# PL_Conenctor.net
KiCad netlist of a schematic drawn in Altium Designer
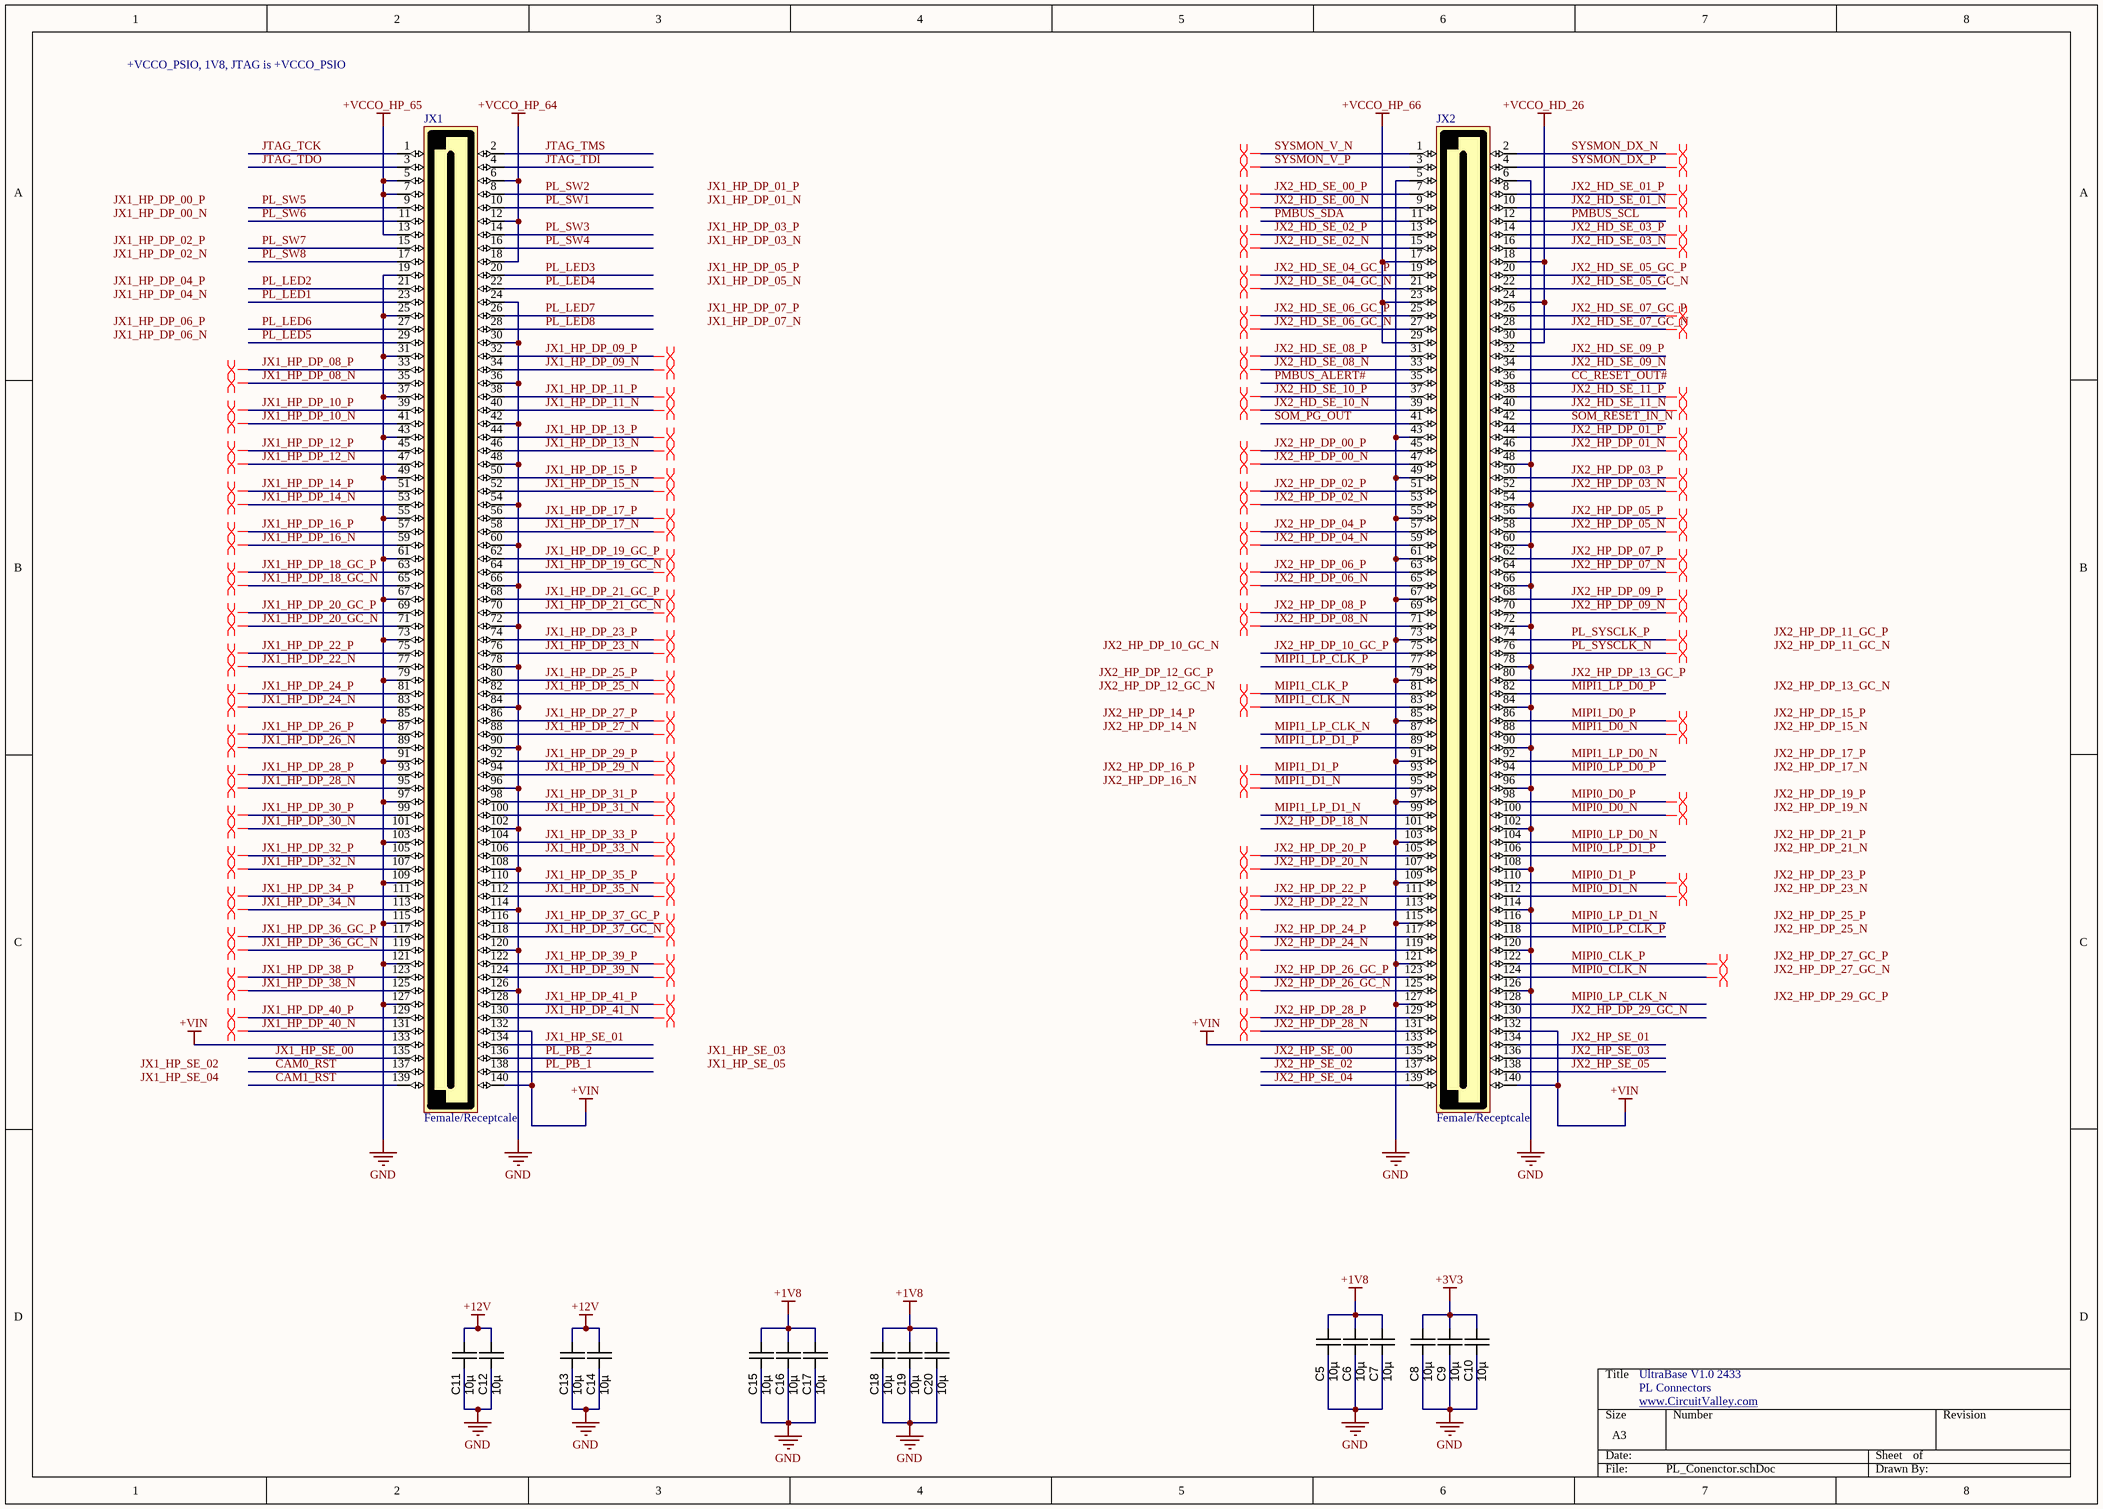
[diagram p0: PL_Conenctor.schDoc]

(export (version "E")
  (design (tool "Eeschema 10.0.6"))
  (components
    (comp (ref "C5")
      (value "10µ")
      (footprint "CAPC3225N")
      (description "Capacitor SMD Cer 10uF 20% 16V X5R 1210")
      (fields (field (name "TOLERANCE") "±20%"))
      (libsource (lib "PBL - Capacitors") (part "CAPC_10u_1210_50V"))
    )
    (comp (ref "C6")
      (value "10µ")
      (footprint "CAPC3225N")
      (description "Capacitor SMD Cer 10uF 20% 16V X5R 1210")
      (fields (field (name "TOLERANCE") "±20%"))
      (libsource (lib "PBL - Capacitors") (part "CAPC_10u_1210_50V"))
    )
    (comp (ref "C7")
      (value "10µ")
      (footprint "CAPC3225N")
      (description "Capacitor SMD Cer 10uF 20% 16V X5R 1210")
      (fields (field (name "TOLERANCE") "±20%"))
      (libsource (lib "PBL - Capacitors") (part "CAPC_10u_1210_50V"))
    )
    (comp (ref "C8")
      (value "10µ")
      (footprint "CAPC3225N")
      (description "Capacitor SMD Cer 10uF 20% 16V X5R 1210")
      (fields (field (name "TOLERANCE") "±20%"))
      (libsource (lib "PBL - Capacitors") (part "CAPC_10u_1210_50V"))
    )
    (comp (ref "C9")
      (value "10µ")
      (footprint "CAPC3225N")
      (description "Capacitor SMD Cer 10uF 20% 16V X5R 1210")
      (fields (field (name "TOLERANCE") "±20%"))
      (libsource (lib "PBL - Capacitors") (part "CAPC_10u_1210_50V"))
    )
    (comp (ref "C10")
      (value "10µ")
      (footprint "CAPC3225N")
      (description "Capacitor SMD Cer 10uF 20% 16V X5R 1210")
      (fields (field (name "TOLERANCE") "±20%"))
      (libsource (lib "PBL - Capacitors") (part "CAPC_10u_1210_50V"))
    )
    (comp (ref "C11")
      (value "10µ")
      (footprint "CAPC3225N")
      (description "Capacitor SMD Cer 10uF 20% 16V X5R 1210")
      (fields (field (name "TOLERANCE") "±20%"))
      (libsource (lib "PBL - Capacitors") (part "CAPC_10u_1210_50V"))
    )
    (comp (ref "C12")
      (value "10µ")
      (footprint "CAPC3225N")
      (description "Capacitor SMD Cer 10uF 20% 16V X5R 1210")
      (fields (field (name "TOLERANCE") "±20%"))
      (libsource (lib "PBL - Capacitors") (part "CAPC_10u_1210_50V"))
    )
    (comp (ref "C13")
      (value "10µ")
      (footprint "CAPC3225N")
      (description "Capacitor SMD Cer 10uF 20% 16V X5R 1210")
      (fields (field (name "TOLERANCE") "±20%"))
      (libsource (lib "PBL - Capacitors") (part "CAPC_10u_1210_50V"))
    )
    (comp (ref "C14")
      (value "10µ")
      (footprint "CAPC3225N")
      (description "Capacitor SMD Cer 10uF 20% 16V X5R 1210")
      (fields (field (name "TOLERANCE") "±20%"))
      (libsource (lib "PBL - Capacitors") (part "CAPC_10u_1210_50V"))
    )
    (comp (ref "C15")
      (value "10µ")
      (footprint "CAPC3225N")
      (description "Capacitor SMD Cer 10uF 20% 16V X5R 1210")
      (fields (field (name "TOLERANCE") "±20%"))
      (libsource (lib "PBL - Capacitors") (part "CAPC_10u_1210_50V"))
    )
    (comp (ref "C16")
      (value "10µ")
      (footprint "CAPC3225N")
      (description "Capacitor SMD Cer 10uF 20% 16V X5R 1210")
      (fields (field (name "TOLERANCE") "±20%"))
      (libsource (lib "PBL - Capacitors") (part "CAPC_10u_1210_50V"))
    )
    (comp (ref "C17")
      (value "10µ")
      (footprint "CAPC3225N")
      (description "Capacitor SMD Cer 10uF 20% 16V X5R 1210")
      (fields (field (name "TOLERANCE") "±20%"))
      (libsource (lib "PBL - Capacitors") (part "CAPC_10u_1210_50V"))
    )
    (comp (ref "C18")
      (value "10µ")
      (footprint "CAPC3225N")
      (description "Capacitor SMD Cer 10uF 20% 16V X5R 1210")
      (fields (field (name "TOLERANCE") "±20%"))
      (libsource (lib "PBL - Capacitors") (part "CAPC_10u_1210_50V"))
    )
    (comp (ref "C19")
      (value "10µ")
      (footprint "CAPC3225N")
      (description "Capacitor SMD Cer 10uF 20% 16V X5R 1210")
      (fields (field (name "TOLERANCE") "±20%"))
      (libsource (lib "PBL - Capacitors") (part "CAPC_10u_1210_50V"))
    )
    (comp (ref "C20")
      (value "10µ")
      (footprint "CAPC3225N")
      (description "Capacitor SMD Cer 10uF 20% 16V X5R 1210")
      (fields (field (name "TOLERANCE") "±20%"))
      (libsource (lib "PBL - Capacitors") (part "CAPC_10u_1210_50V"))
    )
    (comp (ref "JX1")
      (value "Female/Receptcale")
      (footprint "5177985-6")
      (description "140 Pin Ultrascale  SOM Connector with ultrazed specific SOM net delay")
      (libsource (lib "cvlib") (part "5177985-6_Ultrazed_JX1"))
    )
    (comp (ref "JX2")
      (value "Female/Receptcale")
      (footprint "5177985-6")
      (description "140 Pin Ultrascale  SOM Connector with ultrazed specific SOM net delay")
      (libsource (lib "cvlib") (part "5177985-6_Ultrazed_JX2"))
    )
  )
  (nets
    (net (code "1") (name "+1V8") (class "Default")
      (node (ref "C15") (pin "1") (pintype "passive"))
      (node (ref "C16") (pin "1") (pintype "passive"))
      (node (ref "C17") (pin "1") (pintype "passive"))
      (node (ref "C18") (pin "1") (pintype "passive"))
      (node (ref "C19") (pin "1") (pintype "passive"))
      (node (ref "C20") (pin "1") (pintype "passive"))
      (node (ref "C5") (pin "1") (pintype "passive"))
      (node (ref "C6") (pin "1") (pintype "passive"))
      (node (ref "C7") (pin "1") (pintype "passive"))
    )
    (net (code "2") (name "+3V3") (class "Default")
      (node (ref "C10") (pin "1") (pintype "passive"))
      (node (ref "C8") (pin "1") (pintype "passive"))
      (node (ref "C9") (pin "1") (pintype "passive"))
    )
    (net (code "3") (name "+12V") (class "Default")
      (node (ref "C11") (pin "1") (pintype "passive"))
      (node (ref "C12") (pin "1") (pintype "passive"))
      (node (ref "C13") (pin "1") (pintype "passive"))
      (node (ref "C14") (pin "1") (pintype "passive"))
    )
    (net (code "4") (name "+VCCO_HD_26") (class "Default")
      (node (ref "JX2") (pin "18") (pintype "bidirectional"))
      (node (ref "JX2") (pin "24") (pintype "bidirectional"))
      (node (ref "JX2") (pin "30") (pintype "bidirectional"))
    )
    (net (code "5") (name "+VCCO_HP_64") (class "Default")
      (node (ref "JX1") (pin "12") (pintype "bidirectional"))
      (node (ref "JX1") (pin "18") (pintype "bidirectional"))
      (node (ref "JX1") (pin "6") (pintype "bidirectional"))
    )
    (net (code "6") (name "+VCCO_HP_65") (class "Default")
      (node (ref "JX1") (pin "13") (pintype "bidirectional"))
      (node (ref "JX1") (pin "5") (pintype "bidirectional"))
      (node (ref "JX1") (pin "7") (pintype "bidirectional"))
    )
    (net (code "7") (name "+VCCO_HP_66") (class "Default")
      (node (ref "JX2") (pin "17") (pintype "bidirectional"))
      (node (ref "JX2") (pin "23") (pintype "bidirectional"))
      (node (ref "JX2") (pin "29") (pintype "bidirectional"))
    )
    (net (code "8") (name "+VIN") (class "Default")
      (node (ref "JX1") (pin "132") (pintype "bidirectional"))
      (node (ref "JX1") (pin "133") (pintype "bidirectional"))
      (node (ref "JX1") (pin "140") (pintype "bidirectional"))
      (node (ref "JX2") (pin "132") (pintype "bidirectional"))
      (node (ref "JX2") (pin "133") (pintype "bidirectional"))
      (node (ref "JX2") (pin "140") (pintype "bidirectional"))
    )
    (net (code "9") (name "/CAM0_RST") (class "Default")
      (node (ref "JX1") (pin "137") (pintype "bidirectional"))
    )
    (net (code "10") (name "/CAM1_RST") (class "Default")
      (node (ref "JX1") (pin "139") (pintype "bidirectional"))
    )
    (net (code "11") (name "/CC_RESET_OUT#") (class "Default")
      (node (ref "JX2") (pin "36") (pintype "bidirectional"))
    )
    (net (code "12") (name "/JTAG_TCK") (class "Default")
      (node (ref "JX1") (pin "1") (pintype "bidirectional"))
    )
    (net (code "13") (name "/JTAG_TDI") (class "Default")
      (node (ref "JX1") (pin "4") (pintype "bidirectional"))
    )
    (net (code "14") (name "/JTAG_TDO") (class "Default")
      (node (ref "JX1") (pin "3") (pintype "bidirectional"))
    )
    (net (code "15") (name "/JTAG_TMS") (class "Default")
      (node (ref "JX1") (pin "2") (pintype "bidirectional"))
    )
    (net (code "32") (name "/JX1_HP_DP_08_N") (class "Default")
      (node (ref "JX1") (pin "35") (pintype "bidirectional"))
    )
    (net (code "33") (name "/JX1_HP_DP_08_P") (class "Default")
      (node (ref "JX1") (pin "33") (pintype "bidirectional"))
    )
    (net (code "34") (name "/JX1_HP_DP_09_N") (class "Default")
      (node (ref "JX1") (pin "34") (pintype "bidirectional"))
    )
    (net (code "35") (name "/JX1_HP_DP_09_P") (class "Default")
      (node (ref "JX1") (pin "32") (pintype "bidirectional"))
    )
    (net (code "36") (name "/JX1_HP_DP_10_N") (class "Default")
      (node (ref "JX1") (pin "41") (pintype "bidirectional"))
    )
    (net (code "37") (name "/JX1_HP_DP_10_P") (class "Default")
      (node (ref "JX1") (pin "39") (pintype "bidirectional"))
    )
    (net (code "38") (name "/JX1_HP_DP_11_N") (class "Default")
      (node (ref "JX1") (pin "40") (pintype "bidirectional"))
    )
    (net (code "39") (name "/JX1_HP_DP_11_P") (class "Default")
      (node (ref "JX1") (pin "38") (pintype "bidirectional"))
    )
    (net (code "40") (name "/JX1_HP_DP_12_N") (class "Default")
      (node (ref "JX1") (pin "47") (pintype "bidirectional"))
    )
    (net (code "41") (name "/JX1_HP_DP_12_P") (class "Default")
      (node (ref "JX1") (pin "45") (pintype "bidirectional"))
    )
    (net (code "42") (name "/JX1_HP_DP_13_N") (class "Default")
      (node (ref "JX1") (pin "46") (pintype "bidirectional"))
    )
    (net (code "43") (name "/JX1_HP_DP_13_P") (class "Default")
      (node (ref "JX1") (pin "44") (pintype "bidirectional"))
    )
    (net (code "44") (name "/JX1_HP_DP_14_N") (class "Default")
      (node (ref "JX1") (pin "53") (pintype "bidirectional"))
    )
    (net (code "45") (name "/JX1_HP_DP_14_P") (class "Default")
      (node (ref "JX1") (pin "51") (pintype "bidirectional"))
    )
    (net (code "46") (name "/JX1_HP_DP_15_N") (class "Default")
      (node (ref "JX1") (pin "52") (pintype "bidirectional"))
    )
    (net (code "47") (name "/JX1_HP_DP_15_P") (class "Default")
      (node (ref "JX1") (pin "50") (pintype "bidirectional"))
    )
    (net (code "48") (name "/JX1_HP_DP_16_N") (class "Default")
      (node (ref "JX1") (pin "59") (pintype "bidirectional"))
    )
    (net (code "49") (name "/JX1_HP_DP_16_P") (class "Default")
      (node (ref "JX1") (pin "57") (pintype "bidirectional"))
    )
    (net (code "50") (name "/JX1_HP_DP_17_N") (class "Default")
      (node (ref "JX1") (pin "58") (pintype "bidirectional"))
    )
    (net (code "51") (name "/JX1_HP_DP_17_P") (class "Default")
      (node (ref "JX1") (pin "56") (pintype "bidirectional"))
    )
    (net (code "52") (name "/JX1_HP_DP_18_GC_N") (class "Default")
      (node (ref "JX1") (pin "65") (pintype "bidirectional"))
    )
    (net (code "53") (name "/JX1_HP_DP_18_GC_P") (class "Default")
      (node (ref "JX1") (pin "63") (pintype "bidirectional"))
    )
    (net (code "54") (name "/JX1_HP_DP_19_GC_N") (class "Default")
      (node (ref "JX1") (pin "64") (pintype "bidirectional"))
    )
    (net (code "55") (name "/JX1_HP_DP_19_GC_P") (class "Default")
      (node (ref "JX1") (pin "62") (pintype "bidirectional"))
    )
    (net (code "56") (name "/JX1_HP_DP_20_GC_N") (class "Default")
      (node (ref "JX1") (pin "71") (pintype "bidirectional"))
    )
    (net (code "57") (name "/JX1_HP_DP_20_GC_P") (class "Default")
      (node (ref "JX1") (pin "69") (pintype "bidirectional"))
    )
    (net (code "58") (name "/JX1_HP_DP_21_GC_N") (class "Default")
      (node (ref "JX1") (pin "70") (pintype "bidirectional"))
    )
    (net (code "59") (name "/JX1_HP_DP_21_GC_P") (class "Default")
      (node (ref "JX1") (pin "68") (pintype "bidirectional"))
    )
    (net (code "60") (name "/JX1_HP_DP_22_N") (class "Default")
      (node (ref "JX1") (pin "77") (pintype "bidirectional"))
    )
    (net (code "61") (name "/JX1_HP_DP_22_P") (class "Default")
      (node (ref "JX1") (pin "75") (pintype "bidirectional"))
    )
    (net (code "62") (name "/JX1_HP_DP_23_N") (class "Default")
      (node (ref "JX1") (pin "76") (pintype "bidirectional"))
    )
    (net (code "63") (name "/JX1_HP_DP_23_P") (class "Default")
      (node (ref "JX1") (pin "74") (pintype "bidirectional"))
    )
    (net (code "64") (name "/JX1_HP_DP_24_N") (class "Default")
      (node (ref "JX1") (pin "83") (pintype "bidirectional"))
    )
    (net (code "65") (name "/JX1_HP_DP_24_P") (class "Default")
      (node (ref "JX1") (pin "81") (pintype "bidirectional"))
    )
    (net (code "66") (name "/JX1_HP_DP_25_N") (class "Default")
      (node (ref "JX1") (pin "82") (pintype "bidirectional"))
    )
    (net (code "67") (name "/JX1_HP_DP_25_P") (class "Default")
      (node (ref "JX1") (pin "80") (pintype "bidirectional"))
    )
    (net (code "68") (name "/JX1_HP_DP_26_N") (class "Default")
      (node (ref "JX1") (pin "89") (pintype "bidirectional"))
    )
    (net (code "69") (name "/JX1_HP_DP_26_P") (class "Default")
      (node (ref "JX1") (pin "87") (pintype "bidirectional"))
    )
    (net (code "70") (name "/JX1_HP_DP_27_N") (class "Default")
      (node (ref "JX1") (pin "88") (pintype "bidirectional"))
    )
    (net (code "71") (name "/JX1_HP_DP_27_P") (class "Default")
      (node (ref "JX1") (pin "86") (pintype "bidirectional"))
    )
    (net (code "72") (name "/JX1_HP_DP_28_N") (class "Default")
      (node (ref "JX1") (pin "95") (pintype "bidirectional"))
    )
    (net (code "73") (name "/JX1_HP_DP_28_P") (class "Default")
      (node (ref "JX1") (pin "93") (pintype "bidirectional"))
    )
    (net (code "74") (name "/JX1_HP_DP_29_N") (class "Default")
      (node (ref "JX1") (pin "94") (pintype "bidirectional"))
    )
    (net (code "75") (name "/JX1_HP_DP_29_P") (class "Default")
      (node (ref "JX1") (pin "92") (pintype "bidirectional"))
    )
    (net (code "76") (name "/JX1_HP_DP_30_N") (class "Default")
      (node (ref "JX1") (pin "101") (pintype "bidirectional"))
    )
    (net (code "77") (name "/JX1_HP_DP_30_P") (class "Default")
      (node (ref "JX1") (pin "99") (pintype "bidirectional"))
    )
    (net (code "78") (name "/JX1_HP_DP_31_N") (class "Default")
      (node (ref "JX1") (pin "100") (pintype "bidirectional"))
    )
    (net (code "79") (name "/JX1_HP_DP_31_P") (class "Default")
      (node (ref "JX1") (pin "98") (pintype "bidirectional"))
    )
    (net (code "80") (name "/JX1_HP_DP_32_N") (class "Default")
      (node (ref "JX1") (pin "107") (pintype "bidirectional"))
    )
    (net (code "81") (name "/JX1_HP_DP_32_P") (class "Default")
      (node (ref "JX1") (pin "105") (pintype "bidirectional"))
    )
    (net (code "82") (name "/JX1_HP_DP_33_N") (class "Default")
      (node (ref "JX1") (pin "106") (pintype "bidirectional"))
    )
    (net (code "83") (name "/JX1_HP_DP_33_P") (class "Default")
      (node (ref "JX1") (pin "104") (pintype "bidirectional"))
    )
    (net (code "84") (name "/JX1_HP_DP_34_N") (class "Default")
      (node (ref "JX1") (pin "113") (pintype "bidirectional"))
    )
    (net (code "85") (name "/JX1_HP_DP_34_P") (class "Default")
      (node (ref "JX1") (pin "111") (pintype "bidirectional"))
    )
    (net (code "86") (name "/JX1_HP_DP_35_N") (class "Default")
      (node (ref "JX1") (pin "112") (pintype "bidirectional"))
    )
    (net (code "87") (name "/JX1_HP_DP_35_P") (class "Default")
      (node (ref "JX1") (pin "110") (pintype "bidirectional"))
    )
    (net (code "88") (name "/JX1_HP_DP_36_GC_N") (class "Default")
      (node (ref "JX1") (pin "119") (pintype "bidirectional"))
    )
    (net (code "89") (name "/JX1_HP_DP_36_GC_P") (class "Default")
      (node (ref "JX1") (pin "117") (pintype "bidirectional"))
    )
    (net (code "90") (name "/JX1_HP_DP_37_GC_N") (class "Default")
      (node (ref "JX1") (pin "118") (pintype "bidirectional"))
    )
    (net (code "91") (name "/JX1_HP_DP_37_GC_P") (class "Default")
      (node (ref "JX1") (pin "116") (pintype "bidirectional"))
    )
    (net (code "92") (name "/JX1_HP_DP_38_N") (class "Default")
      (node (ref "JX1") (pin "125") (pintype "bidirectional"))
    )
    (net (code "93") (name "/JX1_HP_DP_38_P") (class "Default")
      (node (ref "JX1") (pin "123") (pintype "bidirectional"))
    )
    (net (code "94") (name "/JX1_HP_DP_39_N") (class "Default")
      (node (ref "JX1") (pin "124") (pintype "bidirectional"))
    )
    (net (code "95") (name "/JX1_HP_DP_39_P") (class "Default")
      (node (ref "JX1") (pin "122") (pintype "bidirectional"))
    )
    (net (code "96") (name "/JX1_HP_DP_40_N") (class "Default")
      (node (ref "JX1") (pin "131") (pintype "bidirectional"))
    )
    (net (code "97") (name "/JX1_HP_DP_40_P") (class "Default")
      (node (ref "JX1") (pin "129") (pintype "bidirectional"))
    )
    (net (code "98") (name "/JX1_HP_DP_41_N") (class "Default")
      (node (ref "JX1") (pin "130") (pintype "bidirectional"))
    )
    (net (code "99") (name "/JX1_HP_DP_41_P") (class "Default")
      (node (ref "JX1") (pin "128") (pintype "bidirectional"))
    )
    (net (code "100") (name "/JX1_HP_SE_00") (class "Default")
      (node (ref "JX1") (pin "135") (pintype "bidirectional"))
    )
    (net (code "101") (name "/JX1_HP_SE_01") (class "Default")
      (node (ref "JX1") (pin "134") (pintype "bidirectional"))
    )
    (net (code "106") (name "/JX2_HD_SE_00_N") (class "Default")
      (node (ref "JX2") (pin "9") (pintype "bidirectional"))
    )
    (net (code "107") (name "/JX2_HD_SE_00_P") (class "Default")
      (node (ref "JX2") (pin "7") (pintype "bidirectional"))
    )
    (net (code "108") (name "/JX2_HD_SE_01_N") (class "Default")
      (node (ref "JX2") (pin "10") (pintype "bidirectional"))
    )
    (net (code "109") (name "/JX2_HD_SE_01_P") (class "Default")
      (node (ref "JX2") (pin "8") (pintype "bidirectional"))
    )
    (net (code "110") (name "/JX2_HD_SE_02_N") (class "Default")
      (node (ref "JX2") (pin "15") (pintype "bidirectional"))
    )
    (net (code "111") (name "/JX2_HD_SE_02_P") (class "Default")
      (node (ref "JX2") (pin "13") (pintype "bidirectional"))
    )
    (net (code "112") (name "/JX2_HD_SE_03_N") (class "Default")
      (node (ref "JX2") (pin "16") (pintype "bidirectional"))
    )
    (net (code "113") (name "/JX2_HD_SE_03_P") (class "Default")
      (node (ref "JX2") (pin "14") (pintype "bidirectional"))
    )
    (net (code "114") (name "/JX2_HD_SE_04_GC_N") (class "Default")
      (node (ref "JX2") (pin "21") (pintype "bidirectional"))
    )
    (net (code "115") (name "/JX2_HD_SE_04_GC_P") (class "Default")
      (node (ref "JX2") (pin "19") (pintype "bidirectional"))
    )
    (net (code "116") (name "/JX2_HD_SE_05_GC_N") (class "Default")
      (node (ref "JX2") (pin "22") (pintype "bidirectional"))
    )
    (net (code "117") (name "/JX2_HD_SE_05_GC_P") (class "Default")
      (node (ref "JX2") (pin "20") (pintype "bidirectional"))
    )
    (net (code "118") (name "/JX2_HD_SE_06_GC_N") (class "Default")
      (node (ref "JX2") (pin "27") (pintype "bidirectional"))
    )
    (net (code "119") (name "/JX2_HD_SE_06_GC_P") (class "Default")
      (node (ref "JX2") (pin "25") (pintype "bidirectional"))
    )
    (net (code "120") (name "/JX2_HD_SE_07_GC_N") (class "Default")
      (node (ref "JX2") (pin "28") (pintype "bidirectional"))
    )
    (net (code "121") (name "/JX2_HD_SE_07_GC_P") (class "Default")
      (node (ref "JX2") (pin "26") (pintype "bidirectional"))
    )
    (net (code "122") (name "/JX2_HD_SE_08_N") (class "Default")
      (node (ref "JX2") (pin "33") (pintype "bidirectional"))
    )
    (net (code "123") (name "/JX2_HD_SE_08_P") (class "Default")
      (node (ref "JX2") (pin "31") (pintype "bidirectional"))
    )
    (net (code "124") (name "/JX2_HD_SE_09_N") (class "Default")
      (node (ref "JX2") (pin "34") (pintype "bidirectional"))
    )
    (net (code "125") (name "/JX2_HD_SE_09_P") (class "Default")
      (node (ref "JX2") (pin "32") (pintype "bidirectional"))
    )
    (net (code "126") (name "/JX2_HD_SE_10_N") (class "Default")
      (node (ref "JX2") (pin "39") (pintype "bidirectional"))
    )
    (net (code "127") (name "/JX2_HD_SE_10_P") (class "Default")
      (node (ref "JX2") (pin "37") (pintype "bidirectional"))
    )
    (net (code "128") (name "/JX2_HD_SE_11_N") (class "Default")
      (node (ref "JX2") (pin "40") (pintype "bidirectional"))
    )
    (net (code "129") (name "/JX2_HD_SE_11_P") (class "Default")
      (node (ref "JX2") (pin "38") (pintype "bidirectional"))
    )
    (net (code "130") (name "/JX2_HP_DP_00_N") (class "Default")
      (node (ref "JX2") (pin "47") (pintype "bidirectional"))
    )
    (net (code "131") (name "/JX2_HP_DP_00_P") (class "Default")
      (node (ref "JX2") (pin "45") (pintype "bidirectional"))
    )
    (net (code "132") (name "/JX2_HP_DP_01_N") (class "Default")
      (node (ref "JX2") (pin "46") (pintype "bidirectional"))
    )
    (net (code "133") (name "/JX2_HP_DP_01_P") (class "Default")
      (node (ref "JX2") (pin "44") (pintype "bidirectional"))
    )
    (net (code "134") (name "/JX2_HP_DP_02_N") (class "Default")
      (node (ref "JX2") (pin "53") (pintype "bidirectional"))
    )
    (net (code "135") (name "/JX2_HP_DP_02_P") (class "Default")
      (node (ref "JX2") (pin "51") (pintype "bidirectional"))
    )
    (net (code "136") (name "/JX2_HP_DP_03_N") (class "Default")
      (node (ref "JX2") (pin "52") (pintype "bidirectional"))
    )
    (net (code "137") (name "/JX2_HP_DP_03_P") (class "Default")
      (node (ref "JX2") (pin "50") (pintype "bidirectional"))
    )
    (net (code "138") (name "/JX2_HP_DP_04_N") (class "Default")
      (node (ref "JX2") (pin "59") (pintype "bidirectional"))
    )
    (net (code "139") (name "/JX2_HP_DP_04_P") (class "Default")
      (node (ref "JX2") (pin "57") (pintype "bidirectional"))
    )
    (net (code "140") (name "/JX2_HP_DP_05_N") (class "Default")
      (node (ref "JX2") (pin "58") (pintype "bidirectional"))
    )
    (net (code "141") (name "/JX2_HP_DP_05_P") (class "Default")
      (node (ref "JX2") (pin "56") (pintype "bidirectional"))
    )
    (net (code "142") (name "/JX2_HP_DP_06_N") (class "Default")
      (node (ref "JX2") (pin "65") (pintype "bidirectional"))
    )
    (net (code "143") (name "/JX2_HP_DP_06_P") (class "Default")
      (node (ref "JX2") (pin "63") (pintype "bidirectional"))
    )
    (net (code "144") (name "/JX2_HP_DP_07_N") (class "Default")
      (node (ref "JX2") (pin "64") (pintype "bidirectional"))
    )
    (net (code "145") (name "/JX2_HP_DP_07_P") (class "Default")
      (node (ref "JX2") (pin "62") (pintype "bidirectional"))
    )
    (net (code "146") (name "/JX2_HP_DP_08_N") (class "Default")
      (node (ref "JX2") (pin "71") (pintype "bidirectional"))
    )
    (net (code "147") (name "/JX2_HP_DP_08_P") (class "Default")
      (node (ref "JX2") (pin "69") (pintype "bidirectional"))
    )
    (net (code "148") (name "/JX2_HP_DP_09_N") (class "Default")
      (node (ref "JX2") (pin "70") (pintype "bidirectional"))
    )
    (net (code "149") (name "/JX2_HP_DP_09_P") (class "Default")
      (node (ref "JX2") (pin "68") (pintype "bidirectional"))
    )
    (net (code "151") (name "/JX2_HP_DP_10_GC_P") (class "Default")
      (node (ref "JX2") (pin "75") (pintype "bidirectional"))
    )
    (net (code "157") (name "/JX2_HP_DP_13_GC_P") (class "Default")
      (node (ref "JX2") (pin "80") (pintype "bidirectional"))
    )
    (net (code "166") (name "/JX2_HP_DP_18_N") (class "Default")
      (node (ref "JX2") (pin "101") (pintype "bidirectional"))
    )
    (net (code "169") (name "/JX2_HP_DP_20_N") (class "Default")
      (node (ref "JX2") (pin "107") (pintype "bidirectional"))
    )
    (net (code "170") (name "/JX2_HP_DP_20_P") (class "Default")
      (node (ref "JX2") (pin "105") (pintype "bidirectional"))
    )
    (net (code "173") (name "/JX2_HP_DP_22_N") (class "Default")
      (node (ref "JX2") (pin "113") (pintype "bidirectional"))
    )
    (net (code "174") (name "/JX2_HP_DP_22_P") (class "Default")
      (node (ref "JX2") (pin "111") (pintype "bidirectional"))
    )
    (net (code "177") (name "/JX2_HP_DP_24_N") (class "Default")
      (node (ref "JX2") (pin "119") (pintype "bidirectional"))
    )
    (net (code "178") (name "/JX2_HP_DP_24_P") (class "Default")
      (node (ref "JX2") (pin "117") (pintype "bidirectional"))
    )
    (net (code "181") (name "/JX2_HP_DP_26_GC_N") (class "Default")
      (node (ref "JX2") (pin "125") (pintype "bidirectional"))
    )
    (net (code "182") (name "/JX2_HP_DP_26_GC_P") (class "Default")
      (node (ref "JX2") (pin "123") (pintype "bidirectional"))
    )
    (net (code "185") (name "/JX2_HP_DP_28_N") (class "Default")
      (node (ref "JX2") (pin "131") (pintype "bidirectional"))
    )
    (net (code "186") (name "/JX2_HP_DP_28_P") (class "Default")
      (node (ref "JX2") (pin "129") (pintype "bidirectional"))
    )
    (net (code "187") (name "/JX2_HP_DP_29_GC_N") (class "Default")
      (node (ref "JX2") (pin "130") (pintype "bidirectional"))
    )
    (net (code "189") (name "/JX2_HP_SE_00") (class "Default")
      (node (ref "JX2") (pin "135") (pintype "bidirectional"))
    )
    (net (code "190") (name "/JX2_HP_SE_01") (class "Default")
      (node (ref "JX2") (pin "134") (pintype "bidirectional"))
    )
    (net (code "191") (name "/JX2_HP_SE_02") (class "Default")
      (node (ref "JX2") (pin "137") (pintype "bidirectional"))
    )
    (net (code "192") (name "/JX2_HP_SE_03") (class "Default")
      (node (ref "JX2") (pin "136") (pintype "bidirectional"))
    )
    (net (code "193") (name "/JX2_HP_SE_04") (class "Default")
      (node (ref "JX2") (pin "139") (pintype "bidirectional"))
    )
    (net (code "194") (name "/JX2_HP_SE_05") (class "Default")
      (node (ref "JX2") (pin "138") (pintype "bidirectional"))
    )
    (net (code "195") (name "/MIPI0_CLK_N") (class "Default")
      (node (ref "JX2") (pin "124") (pintype "bidirectional"))
    )
    (net (code "196") (name "/MIPI0_CLK_P") (class "Default")
      (node (ref "JX2") (pin "122") (pintype "bidirectional"))
    )
    (net (code "197") (name "/MIPI0_D0_N") (class "Default")
      (node (ref "JX2") (pin "100") (pintype "bidirectional"))
    )
    (net (code "198") (name "/MIPI0_D0_P") (class "Default")
      (node (ref "JX2") (pin "98") (pintype "bidirectional"))
    )
    (net (code "199") (name "/MIPI0_D1_N") (class "Default")
      (node (ref "JX2") (pin "112") (pintype "bidirectional"))
    )
    (net (code "200") (name "/MIPI0_D1_P") (class "Default")
      (node (ref "JX2") (pin "110") (pintype "bidirectional"))
    )
    (net (code "201") (name "/MIPI0_LP_CLK_N") (class "Default")
      (node (ref "JX2") (pin "128") (pintype "bidirectional"))
    )
    (net (code "202") (name "/MIPI0_LP_CLK_P") (class "Default")
      (node (ref "JX2") (pin "118") (pintype "bidirectional"))
    )
    (net (code "203") (name "/MIPI0_LP_D0_N") (class "Default")
      (node (ref "JX2") (pin "104") (pintype "bidirectional"))
    )
    (net (code "204") (name "/MIPI0_LP_D0_P") (class "Default")
      (node (ref "JX2") (pin "94") (pintype "bidirectional"))
    )
    (net (code "205") (name "/MIPI0_LP_D1_N") (class "Default")
      (node (ref "JX2") (pin "116") (pintype "bidirectional"))
    )
    (net (code "206") (name "/MIPI0_LP_D1_P") (class "Default")
      (node (ref "JX2") (pin "106") (pintype "bidirectional"))
    )
    (net (code "207") (name "/MIPI1_CLK_N") (class "Default")
      (node (ref "JX2") (pin "83") (pintype "bidirectional"))
    )
    (net (code "208") (name "/MIPI1_CLK_P") (class "Default")
      (node (ref "JX2") (pin "81") (pintype "bidirectional"))
    )
    (net (code "209") (name "/MIPI1_D0_N") (class "Default")
      (node (ref "JX2") (pin "88") (pintype "bidirectional"))
    )
    (net (code "210") (name "/MIPI1_D0_P") (class "Default")
      (node (ref "JX2") (pin "86") (pintype "bidirectional"))
    )
    (net (code "211") (name "/MIPI1_D1_N") (class "Default")
      (node (ref "JX2") (pin "95") (pintype "bidirectional"))
    )
    (net (code "212") (name "/MIPI1_D1_P") (class "Default")
      (node (ref "JX2") (pin "93") (pintype "bidirectional"))
    )
    (net (code "213") (name "/MIPI1_LP_CLK_N") (class "Default")
      (node (ref "JX2") (pin "87") (pintype "bidirectional"))
    )
    (net (code "214") (name "/MIPI1_LP_CLK_P") (class "Default")
      (node (ref "JX2") (pin "77") (pintype "bidirectional"))
    )
    (net (code "215") (name "/MIPI1_LP_D0_N") (class "Default")
      (node (ref "JX2") (pin "92") (pintype "bidirectional"))
    )
    (net (code "216") (name "/MIPI1_LP_D0_P") (class "Default")
      (node (ref "JX2") (pin "82") (pintype "bidirectional"))
    )
    (net (code "217") (name "/MIPI1_LP_D1_N") (class "Default")
      (node (ref "JX2") (pin "99") (pintype "bidirectional"))
    )
    (net (code "218") (name "/MIPI1_LP_D1_P") (class "Default")
      (node (ref "JX2") (pin "89") (pintype "bidirectional"))
    )
    (net (code "219") (name "/PL_LED1") (class "Default")
      (node (ref "JX1") (pin "23") (pintype "bidirectional"))
    )
    (net (code "220") (name "/PL_LED2") (class "Default")
      (node (ref "JX1") (pin "21") (pintype "bidirectional"))
    )
    (net (code "221") (name "/PL_LED3") (class "Default")
      (node (ref "JX1") (pin "20") (pintype "bidirectional"))
    )
    (net (code "222") (name "/PL_LED4") (class "Default")
      (node (ref "JX1") (pin "22") (pintype "bidirectional"))
    )
    (net (code "223") (name "/PL_LED5") (class "Default")
      (node (ref "JX1") (pin "29") (pintype "bidirectional"))
    )
    (net (code "224") (name "/PL_LED6") (class "Default")
      (node (ref "JX1") (pin "27") (pintype "bidirectional"))
    )
    (net (code "225") (name "/PL_LED7") (class "Default")
      (node (ref "JX1") (pin "26") (pintype "bidirectional"))
    )
    (net (code "226") (name "/PL_LED8") (class "Default")
      (node (ref "JX1") (pin "28") (pintype "bidirectional"))
    )
    (net (code "227") (name "/PL_PB_1") (class "Default")
      (node (ref "JX1") (pin "138") (pintype "bidirectional"))
    )
    (net (code "228") (name "/PL_PB_2") (class "Default")
      (node (ref "JX1") (pin "136") (pintype "bidirectional"))
    )
    (net (code "229") (name "/PL_SW1") (class "Default")
      (node (ref "JX1") (pin "10") (pintype "bidirectional"))
    )
    (net (code "230") (name "/PL_SW2") (class "Default")
      (node (ref "JX1") (pin "8") (pintype "bidirectional"))
    )
    (net (code "231") (name "/PL_SW3") (class "Default")
      (node (ref "JX1") (pin "14") (pintype "bidirectional"))
    )
    (net (code "232") (name "/PL_SW4") (class "Default")
      (node (ref "JX1") (pin "16") (pintype "bidirectional"))
    )
    (net (code "233") (name "/PL_SW5") (class "Default")
      (node (ref "JX1") (pin "9") (pintype "bidirectional"))
    )
    (net (code "234") (name "/PL_SW6") (class "Default")
      (node (ref "JX1") (pin "11") (pintype "bidirectional"))
    )
    (net (code "235") (name "/PL_SW7") (class "Default")
      (node (ref "JX1") (pin "15") (pintype "bidirectional"))
    )
    (net (code "236") (name "/PL_SW8") (class "Default")
      (node (ref "JX1") (pin "17") (pintype "bidirectional"))
    )
    (net (code "237") (name "/PL_SYSCLK_N") (class "Default")
      (node (ref "JX2") (pin "76") (pintype "bidirectional"))
    )
    (net (code "238") (name "/PL_SYSCLK_P") (class "Default")
      (node (ref "JX2") (pin "74") (pintype "bidirectional"))
    )
    (net (code "239") (name "/PMBUS_ALERT#") (class "Default")
      (node (ref "JX2") (pin "35") (pintype "bidirectional"))
    )
    (net (code "240") (name "/PMBUS_SCL") (class "Default")
      (node (ref "JX2") (pin "12") (pintype "bidirectional"))
    )
    (net (code "241") (name "/PMBUS_SDA") (class "Default")
      (node (ref "JX2") (pin "11") (pintype "bidirectional"))
    )
    (net (code "242") (name "/SOM_PG_OUT") (class "Default")
      (node (ref "JX2") (pin "41") (pintype "bidirectional"))
    )
    (net (code "243") (name "/SOM_RESET_IN_N") (class "Default")
      (node (ref "JX2") (pin "42") (pintype "bidirectional"))
    )
    (net (code "244") (name "/SYSMON_DX_N") (class "Default")
      (node (ref "JX2") (pin "2") (pintype "bidirectional"))
    )
    (net (code "245") (name "/SYSMON_DX_P") (class "Default")
      (node (ref "JX2") (pin "4") (pintype "bidirectional"))
    )
    (net (code "246") (name "/SYSMON_V_N") (class "Default")
      (node (ref "JX2") (pin "1") (pintype "bidirectional"))
    )
    (net (code "247") (name "/SYSMON_V_P") (class "Default")
      (node (ref "JX2") (pin "3") (pintype "bidirectional"))
    )
    (net (code "248") (name "GND") (class "Default")
      (node (ref "C10") (pin "2") (pintype "passive"))
      (node (ref "C11") (pin "2") (pintype "passive"))
      (node (ref "C12") (pin "2") (pintype "passive"))
      (node (ref "C13") (pin "2") (pintype "passive"))
      (node (ref "C14") (pin "2") (pintype "passive"))
      (node (ref "C15") (pin "2") (pintype "passive"))
      (node (ref "C16") (pin "2") (pintype "passive"))
      (node (ref "C17") (pin "2") (pintype "passive"))
      (node (ref "C18") (pin "2") (pintype "passive"))
      (node (ref "C19") (pin "2") (pintype "passive"))
      (node (ref "C20") (pin "2") (pintype "passive"))
      (node (ref "C5") (pin "2") (pintype "passive"))
      (node (ref "C6") (pin "2") (pintype "passive"))
      (node (ref "C7") (pin "2") (pintype "passive"))
      (node (ref "C8") (pin "2") (pintype "passive"))
      (node (ref "C9") (pin "2") (pintype "passive"))
      (node (ref "JX1") (pin "102") (pintype "bidirectional"))
      (node (ref "JX1") (pin "103") (pintype "bidirectional"))
      (node (ref "JX1") (pin "108") (pintype "bidirectional"))
      (node (ref "JX1") (pin "109") (pintype "bidirectional"))
      (node (ref "JX1") (pin "114") (pintype "bidirectional"))
      (node (ref "JX1") (pin "115") (pintype "bidirectional"))
      (node (ref "JX1") (pin "120") (pintype "bidirectional"))
      (node (ref "JX1") (pin "121") (pintype "bidirectional"))
      (node (ref "JX1") (pin "126") (pintype "bidirectional"))
      (node (ref "JX1") (pin "127") (pintype "bidirectional"))
      (node (ref "JX1") (pin "19") (pintype "bidirectional"))
      (node (ref "JX1") (pin "24") (pintype "bidirectional"))
      (node (ref "JX1") (pin "25") (pintype "bidirectional"))
      (node (ref "JX1") (pin "30") (pintype "bidirectional"))
      (node (ref "JX1") (pin "31") (pintype "bidirectional"))
      (node (ref "JX1") (pin "36") (pintype "bidirectional"))
      (node (ref "JX1") (pin "37") (pintype "bidirectional"))
      (node (ref "JX1") (pin "42") (pintype "bidirectional"))
      (node (ref "JX1") (pin "43") (pintype "bidirectional"))
      (node (ref "JX1") (pin "48") (pintype "bidirectional"))
      (node (ref "JX1") (pin "49") (pintype "bidirectional"))
      (node (ref "JX1") (pin "54") (pintype "bidirectional"))
      (node (ref "JX1") (pin "55") (pintype "bidirectional"))
      (node (ref "JX1") (pin "60") (pintype "bidirectional"))
      (node (ref "JX1") (pin "61") (pintype "bidirectional"))
      (node (ref "JX1") (pin "66") (pintype "bidirectional"))
      (node (ref "JX1") (pin "67") (pintype "bidirectional"))
      (node (ref "JX1") (pin "72") (pintype "bidirectional"))
      (node (ref "JX1") (pin "73") (pintype "bidirectional"))
      (node (ref "JX1") (pin "78") (pintype "bidirectional"))
      (node (ref "JX1") (pin "79") (pintype "bidirectional"))
      (node (ref "JX1") (pin "84") (pintype "bidirectional"))
      (node (ref "JX1") (pin "85") (pintype "bidirectional"))
      (node (ref "JX1") (pin "90") (pintype "bidirectional"))
      (node (ref "JX1") (pin "91") (pintype "bidirectional"))
      (node (ref "JX1") (pin "96") (pintype "bidirectional"))
      (node (ref "JX1") (pin "97") (pintype "bidirectional"))
      (node (ref "JX2") (pin "102") (pintype "bidirectional"))
      (node (ref "JX2") (pin "103") (pintype "bidirectional"))
      (node (ref "JX2") (pin "108") (pintype "bidirectional"))
      (node (ref "JX2") (pin "109") (pintype "bidirectional"))
      (node (ref "JX2") (pin "114") (pintype "bidirectional"))
      (node (ref "JX2") (pin "115") (pintype "bidirectional"))
      (node (ref "JX2") (pin "120") (pintype "bidirectional"))
      (node (ref "JX2") (pin "121") (pintype "bidirectional"))
      (node (ref "JX2") (pin "126") (pintype "bidirectional"))
      (node (ref "JX2") (pin "127") (pintype "bidirectional"))
      (node (ref "JX2") (pin "43") (pintype "bidirectional"))
      (node (ref "JX2") (pin "48") (pintype "bidirectional"))
      (node (ref "JX2") (pin "49") (pintype "bidirectional"))
      (node (ref "JX2") (pin "5") (pintype "bidirectional"))
      (node (ref "JX2") (pin "54") (pintype "bidirectional"))
      (node (ref "JX2") (pin "55") (pintype "bidirectional"))
      (node (ref "JX2") (pin "6") (pintype "bidirectional"))
      (node (ref "JX2") (pin "60") (pintype "bidirectional"))
      (node (ref "JX2") (pin "61") (pintype "bidirectional"))
      (node (ref "JX2") (pin "66") (pintype "bidirectional"))
      (node (ref "JX2") (pin "67") (pintype "bidirectional"))
      (node (ref "JX2") (pin "72") (pintype "bidirectional"))
      (node (ref "JX2") (pin "73") (pintype "bidirectional"))
      (node (ref "JX2") (pin "78") (pintype "bidirectional"))
      (node (ref "JX2") (pin "79") (pintype "bidirectional"))
      (node (ref "JX2") (pin "84") (pintype "bidirectional"))
      (node (ref "JX2") (pin "85") (pintype "bidirectional"))
      (node (ref "JX2") (pin "90") (pintype "bidirectional"))
      (node (ref "JX2") (pin "91") (pintype "bidirectional"))
      (node (ref "JX2") (pin "96") (pintype "bidirectional"))
      (node (ref "JX2") (pin "97") (pintype "bidirectional"))
    )
  )
)
